# Sheet1.net
KiCad netlist of a schematic drawn in Altium Designer
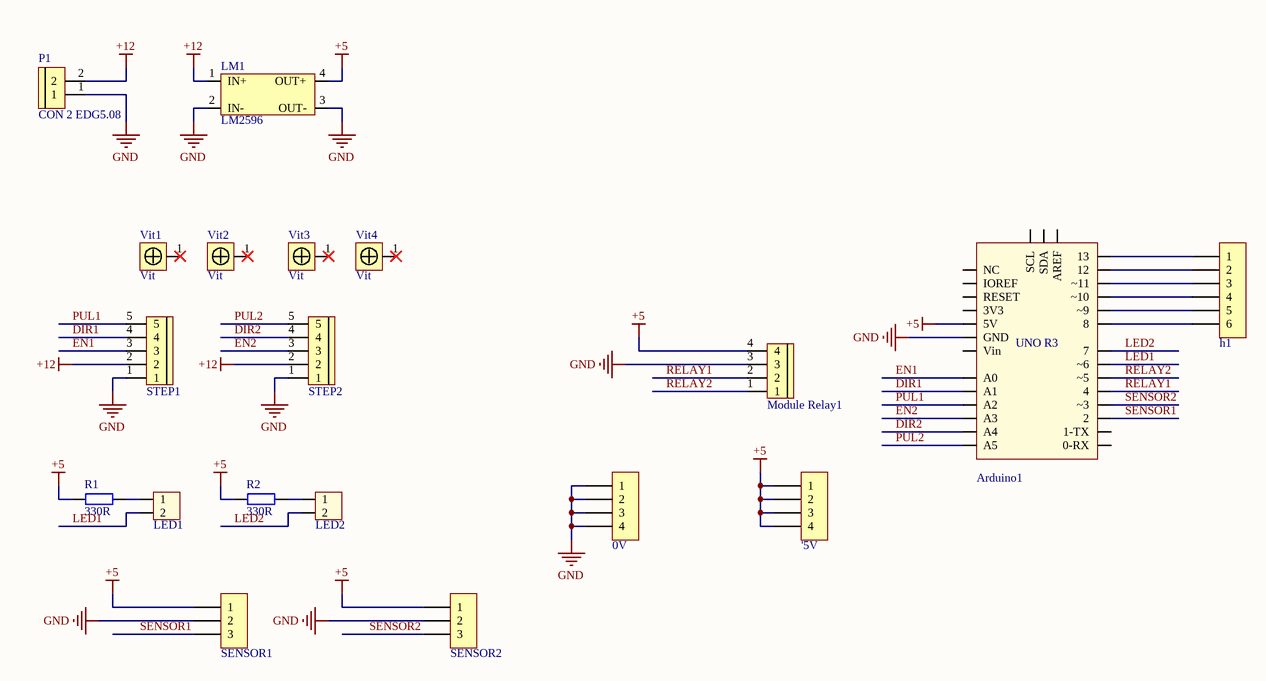
[diagram p0: Sheet1.SchDoc]

(export (version "E")
  (design (tool "Eeschema 10.0.6"))
  (components
    (comp (ref "Arduino1")
      (value "Arduino Uno R3")
      (footprint "Arduino UNO R3")
      (description "Arduino UNO R3")
      (libsource (lib "TechMT.VN_Lib_Project v2") (part "Arduino Uno R3"))
    )
    (comp (ref "H1")
      (value "h1")
      (footprint "XH2.54M-6")
      (description "Cắm")
      (libsource (lib "Altium_Lib_by_KhueNguyenCreator") (part "Header 6P 2.54 Duc Thang"))
    )
    (comp (ref "H2")
      (value "0V")
      (footprint "XH2.54M-4")
      (description "Cắm")
      (libsource (lib "Altium_Lib_by_KhueNguyenCreator") (part "Header 4P 2.54 Duc Thang"))
    )
    (comp (ref "H3")
      (value "'5V")
      (footprint "XH2.54M-4")
      (description "Cắm")
      (libsource (lib "Altium_Lib_by_KhueNguyenCreator") (part "Header 4P 2.54 Duc Thang"))
    )
    (comp (ref "H4")
      (value "LED1")
      (footprint "XH2.54M-2")
      (description "Cắm")
      (libsource (lib "Altium_Lib_by_KhueNguyenCreator") (part "Header 2P 2.54 Duc Thang"))
    )
    (comp (ref "H5")
      (value "LED2")
      (footprint "XH2.54M-2")
      (description "Cắm")
      (libsource (lib "Altium_Lib_by_KhueNguyenCreator") (part "Header 2P 2.54 Duc Thang"))
    )
    (comp (ref "H6")
      (value "SENSOR1")
      (footprint "XH2.54M-3")
      (description "Cắm")
      (libsource (lib "Altium_Lib_by_KhueNguyenCreator") (part "Header 3P 2.54 Duc Thang"))
    )
    (comp (ref "H7")
      (value "SENSOR2")
      (footprint "XH2.54M-3")
      (description "Cắm")
      (libsource (lib "Altium_Lib_by_KhueNguyenCreator") (part "Header 3P 2.54 Duc Thang"))
    )
    (comp (ref "LM1")
      (value "LM2596")
      (footprint "LM2596_Module")
      (libsource (lib "MyLib") (part "LM2596_Module"))
    )
    (comp (ref "Module Relay1")
      (value "CON 4 EDG5.08")
      (footprint "CON 4 4EDG5.08")
      (description "Cắm")
      (libsource (lib "Altium_Lib_by_KhueNguyenCreator") (part "CON 4 EDG5.08"))
    )
    (comp (ref "P1")
      (value "CON 2 EDG5.08")
      (footprint "CON 2 2EDG5.08")
      (description "Cắm")
      (libsource (lib "Altium_Lib_by_KhueNguyenCreator") (part "CON 2 EDG5.08"))
    )
    (comp (ref "R1")
      (value "330R")
      (footprint "tro vach 1/4w")
      (description "Cắm")
      (libsource (lib "Altium_Lib_by_KhueNguyenCreator") (part "Tro Vach 1/4W 1% 330R"))
    )
    (comp (ref "R2")
      (value "330R")
      (footprint "tro vach 1/4w")
      (description "Cắm")
      (libsource (lib "Altium_Lib_by_KhueNguyenCreator") (part "Tro Vach 1/4W 1% 330R"))
    )
    (comp (ref "STEP1")
      (value "CON 5 EDG5.08")
      (footprint "CON 5 5EDG5.08")
      (description "Cắm")
      (libsource (lib "Altium_Lib_by_KhueNguyenCreator") (part "CON 5 EDG5.08"))
    )
    (comp (ref "STEP2")
      (value "CON 5 EDG5.08")
      (footprint "CON 5 5EDG5.08")
      (description "Cắm")
      (libsource (lib "Altium_Lib_by_KhueNguyenCreator") (part "CON 5 EDG5.08"))
    )
    (comp (ref "Vit1") (value "Vit") (footprint "Vit M3") (libsource (lib "MyLib") (part "Vit")))
    (comp (ref "Vit2") (value "Vit") (footprint "Vit M3") (libsource (lib "MyLib") (part "Vit")))
    (comp (ref "Vit3") (value "Vit") (footprint "Vit M3") (libsource (lib "MyLib") (part "Vit")))
    (comp (ref "Vit4") (value "Vit") (footprint "Vit M3") (libsource (lib "MyLib") (part "Vit")))
  )
  (nets
    (net (code "1") (name "+5") (class "Default")
      (node (ref "Arduino1") (pin "5V") (pinfunction "5V_5V") (pintype "passive"))
      (node (ref "H3") (pin "1") (pinfunction "1_1") (pintype "passive"))
      (node (ref "H3") (pin "2") (pinfunction "2_2") (pintype "passive"))
      (node (ref "H3") (pin "3") (pinfunction "3_3") (pintype "passive"))
      (node (ref "H3") (pin "4") (pinfunction "4_4") (pintype "passive"))
      (node (ref "H6") (pin "1") (pinfunction "1_1") (pintype "passive"))
      (node (ref "H7") (pin "1") (pinfunction "1_1") (pintype "passive"))
      (node (ref "LM1") (pin "4") (pinfunction "OUT+_4") (pintype "passive"))
      (node (ref "Module Relay1") (pin "4") (pinfunction "4_4") (pintype "passive"))
      (node (ref "R1") (pin "1") (pinfunction "1_1") (pintype "passive"))
      (node (ref "R2") (pin "1") (pinfunction "1_1") (pintype "passive"))
    )
    (net (code "2") (name "+12") (class "Default")
      (node (ref "LM1") (pin "1") (pinfunction "IN+_1") (pintype "passive"))
      (node (ref "P1") (pin "2") (pinfunction "2_2") (pintype "passive"))
      (node (ref "STEP1") (pin "2") (pinfunction "2_2") (pintype "passive"))
      (node (ref "STEP2") (pin "2") (pinfunction "2_2") (pintype "passive"))
    )
    (net (code "3") (name "/DIR1") (class "Default")
      (node (ref "Arduino1") (pin "A1") (pinfunction "A1_A1") (pintype "passive"))
      (node (ref "STEP1") (pin "4") (pinfunction "4_4") (pintype "passive"))
    )
    (net (code "4") (name "/DIR2") (class "Default")
      (node (ref "Arduino1") (pin "A4") (pinfunction "A4_A4") (pintype "passive"))
      (node (ref "STEP2") (pin "4") (pinfunction "4_4") (pintype "passive"))
    )
    (net (code "5") (name "/EN1") (class "Default")
      (node (ref "Arduino1") (pin "A0") (pinfunction "A0_A0") (pintype "passive"))
      (node (ref "STEP1") (pin "3") (pinfunction "3_3") (pintype "passive"))
    )
    (net (code "6") (name "/EN2") (class "Default")
      (node (ref "Arduino1") (pin "A3") (pinfunction "A3_A3") (pintype "passive"))
      (node (ref "STEP2") (pin "3") (pinfunction "3_3") (pintype "passive"))
    )
    (net (code "7") (name "/LED1") (class "Default")
      (node (ref "Arduino1") (pin "~6") (pinfunction "~6_~6") (pintype "passive"))
      (node (ref "H4") (pin "2") (pinfunction "2_2") (pintype "passive"))
    )
    (net (code "8") (name "/LED2") (class "Default")
      (node (ref "Arduino1") (pin "7") (pinfunction "7_7") (pintype "passive"))
      (node (ref "H5") (pin "2") (pinfunction "2_2") (pintype "passive"))
    )
    (net (code "9") (name "/PUL1") (class "Default")
      (node (ref "Arduino1") (pin "A2") (pinfunction "A2_A2") (pintype "passive"))
      (node (ref "STEP1") (pin "5") (pinfunction "5_5") (pintype "passive"))
    )
    (net (code "10") (name "/PUL2") (class "Default")
      (node (ref "Arduino1") (pin "A5") (pinfunction "A5_A5") (pintype "passive"))
      (node (ref "STEP2") (pin "5") (pinfunction "5_5") (pintype "passive"))
    )
    (net (code "11") (name "/RELAY1") (class "Default")
      (node (ref "Arduino1") (pin "4") (pinfunction "4_4") (pintype "passive"))
      (node (ref "Module Relay1") (pin "2") (pinfunction "2_2") (pintype "passive"))
    )
    (net (code "12") (name "/RELAY2") (class "Default")
      (node (ref "Arduino1") (pin "~5") (pinfunction "~5_~5") (pintype "passive"))
      (node (ref "Module Relay1") (pin "1") (pinfunction "1_1") (pintype "passive"))
    )
    (net (code "13") (name "/SENSOR1") (class "Default")
      (node (ref "Arduino1") (pin "2") (pinfunction "2_2") (pintype "passive"))
      (node (ref "H6") (pin "3") (pinfunction "3_3") (pintype "passive"))
    )
    (net (code "14") (name "/SENSOR2") (class "Default")
      (node (ref "Arduino1") (pin "~3") (pinfunction "~3_~3") (pintype "passive"))
      (node (ref "H7") (pin "3") (pinfunction "3_3") (pintype "passive"))
    )
    (net (code "15") (name "GND") (class "Default")
      (node (ref "Arduino1") (pin "GND") (pinfunction "GND_GND") (pintype "passive"))
      (node (ref "H2") (pin "1") (pinfunction "1_1") (pintype "passive"))
      (node (ref "H2") (pin "2") (pinfunction "2_2") (pintype "passive"))
      (node (ref "H2") (pin "3") (pinfunction "3_3") (pintype "passive"))
      (node (ref "H2") (pin "4") (pinfunction "4_4") (pintype "passive"))
      (node (ref "H6") (pin "2") (pinfunction "2_2") (pintype "passive"))
      (node (ref "H7") (pin "2") (pinfunction "2_2") (pintype "passive"))
      (node (ref "LM1") (pin "2") (pinfunction "IN-_2") (pintype "passive"))
      (node (ref "LM1") (pin "3") (pinfunction "OUT-_3") (pintype "passive"))
      (node (ref "Module Relay1") (pin "3") (pinfunction "3_3") (pintype "passive"))
      (node (ref "P1") (pin "1") (pinfunction "1_1") (pintype "passive"))
      (node (ref "STEP1") (pin "1") (pinfunction "1_1") (pintype "passive"))
      (node (ref "STEP2") (pin "1") (pinfunction "1_1") (pintype "passive"))
    )
    (net (code "16") (name "Net-(Arduino1-Pad8)") (class "Default")
      (node (ref "Arduino1") (pin "8") (pinfunction "8_8") (pintype "passive"))
      (node (ref "H1") (pin "6") (pinfunction "6_6") (pintype "passive"))
    )
    (net (code "17") (name "Net-(Arduino1-Pad12)") (class "Default")
      (node (ref "Arduino1") (pin "12") (pinfunction "12_12") (pintype "passive"))
      (node (ref "H1") (pin "2") (pinfunction "2_2") (pintype "passive"))
    )
    (net (code "18") (name "Net-(Arduino1-Pad13)") (class "Default")
      (node (ref "Arduino1") (pin "13") (pinfunction "13_13") (pintype "passive"))
      (node (ref "H1") (pin "1") (pinfunction "1_1") (pintype "passive"))
    )
    (net (code "19") (name "Net-(Arduino1-Pad~9)") (class "Default")
      (node (ref "Arduino1") (pin "~9") (pinfunction "~9_~9") (pintype "passive"))
      (node (ref "H1") (pin "5") (pinfunction "5_5") (pintype "passive"))
    )
    (net (code "20") (name "Net-(Arduino1-Pad~10)") (class "Default")
      (node (ref "Arduino1") (pin "~10") (pinfunction "~10_~10") (pintype "passive"))
      (node (ref "H1") (pin "4") (pinfunction "4_4") (pintype "passive"))
    )
    (net (code "21") (name "Net-(Arduino1-Pad~11)") (class "Default")
      (node (ref "Arduino1") (pin "~11") (pinfunction "~11_~11") (pintype "passive"))
      (node (ref "H1") (pin "3") (pinfunction "3_3") (pintype "passive"))
    )
    (net (code "22") (name "Net-(H4-Pad1)") (class "Default")
      (node (ref "H4") (pin "1") (pinfunction "1_1") (pintype "passive"))
      (node (ref "R1") (pin "2") (pinfunction "2_2") (pintype "passive"))
    )
    (net (code "23") (name "Net-(H5-Pad1)") (class "Default")
      (node (ref "H5") (pin "1") (pinfunction "1_1") (pintype "passive"))
      (node (ref "R2") (pin "2") (pinfunction "2_2") (pintype "passive"))
    )
    (net (code "24") (name "unconnected-(Arduino1-Pad0-RX)") (class "Default")
      (node (ref "Arduino1") (pin "0-RX") (pinfunction "0-RX_0-RX") (pintype "passive"))
    )
    (net (code "25") (name "unconnected-(Arduino1-Pad1-TX)") (class "Default")
      (node (ref "Arduino1") (pin "1-TX") (pinfunction "1-TX_1-TX") (pintype "passive"))
    )
    (net (code "26") (name "unconnected-(Arduino1-Pad3V3)") (class "Default")
      (node (ref "Arduino1") (pin "3V3") (pinfunction "3V3_3V3") (pintype "passive"))
    )
    (net (code "27") (name "unconnected-(Arduino1-PadAREF)") (class "Default")
      (node (ref "Arduino1") (pin "AREF") (pinfunction "AREF_AREF") (pintype "passive"))
    )
    (net (code "28") (name "unconnected-(Arduino1-PadIOREF)") (class "Default")
      (node (ref "Arduino1") (pin "IOREF") (pinfunction "IOREF_IOREF") (pintype "passive"))
    )
    (net (code "29") (name "unconnected-(Arduino1-PadNC)") (class "Default")
      (node (ref "Arduino1") (pin "NC") (pinfunction "NC_NC") (pintype "passive"))
    )
    (net (code "30") (name "unconnected-(Arduino1-PadRESET)") (class "Default")
      (node (ref "Arduino1") (pin "RESET") (pinfunction "RESET_RESET") (pintype "passive"))
    )
    (net (code "31") (name "unconnected-(Arduino1-PadSCL)") (class "Default")
      (node (ref "Arduino1") (pin "SCL") (pinfunction "SCL_SCL") (pintype "passive"))
    )
    (net (code "32") (name "unconnected-(Arduino1-PadSDA)") (class "Default")
      (node (ref "Arduino1") (pin "SDA") (pinfunction "SDA_SDA") (pintype "passive"))
    )
    (net (code "33") (name "unconnected-(Arduino1-PadVin)") (class "Default")
      (node (ref "Arduino1") (pin "Vin") (pinfunction "Vin_Vin") (pintype "passive"))
    )
    (net (code "34") (name "unconnected-(Vit1-13-Pad1)") (class "Default")
      (node (ref "Vit1") (pin "1") (pinfunction "13_1") (pintype "passive+no_connect"))
    )
    (net (code "35") (name "unconnected-(Vit2-13-Pad1)") (class "Default")
      (node (ref "Vit2") (pin "1") (pinfunction "13_1") (pintype "passive+no_connect"))
    )
    (net (code "36") (name "unconnected-(Vit3-13-Pad1)") (class "Default")
      (node (ref "Vit3") (pin "1") (pinfunction "13_1") (pintype "passive+no_connect"))
    )
    (net (code "37") (name "unconnected-(Vit4-13-Pad1)") (class "Default")
      (node (ref "Vit4") (pin "1") (pinfunction "13_1") (pintype "passive+no_connect"))
    )
  )
)
